# stm8core.net
KiCad netlist of a schematic drawn in Altium Designer
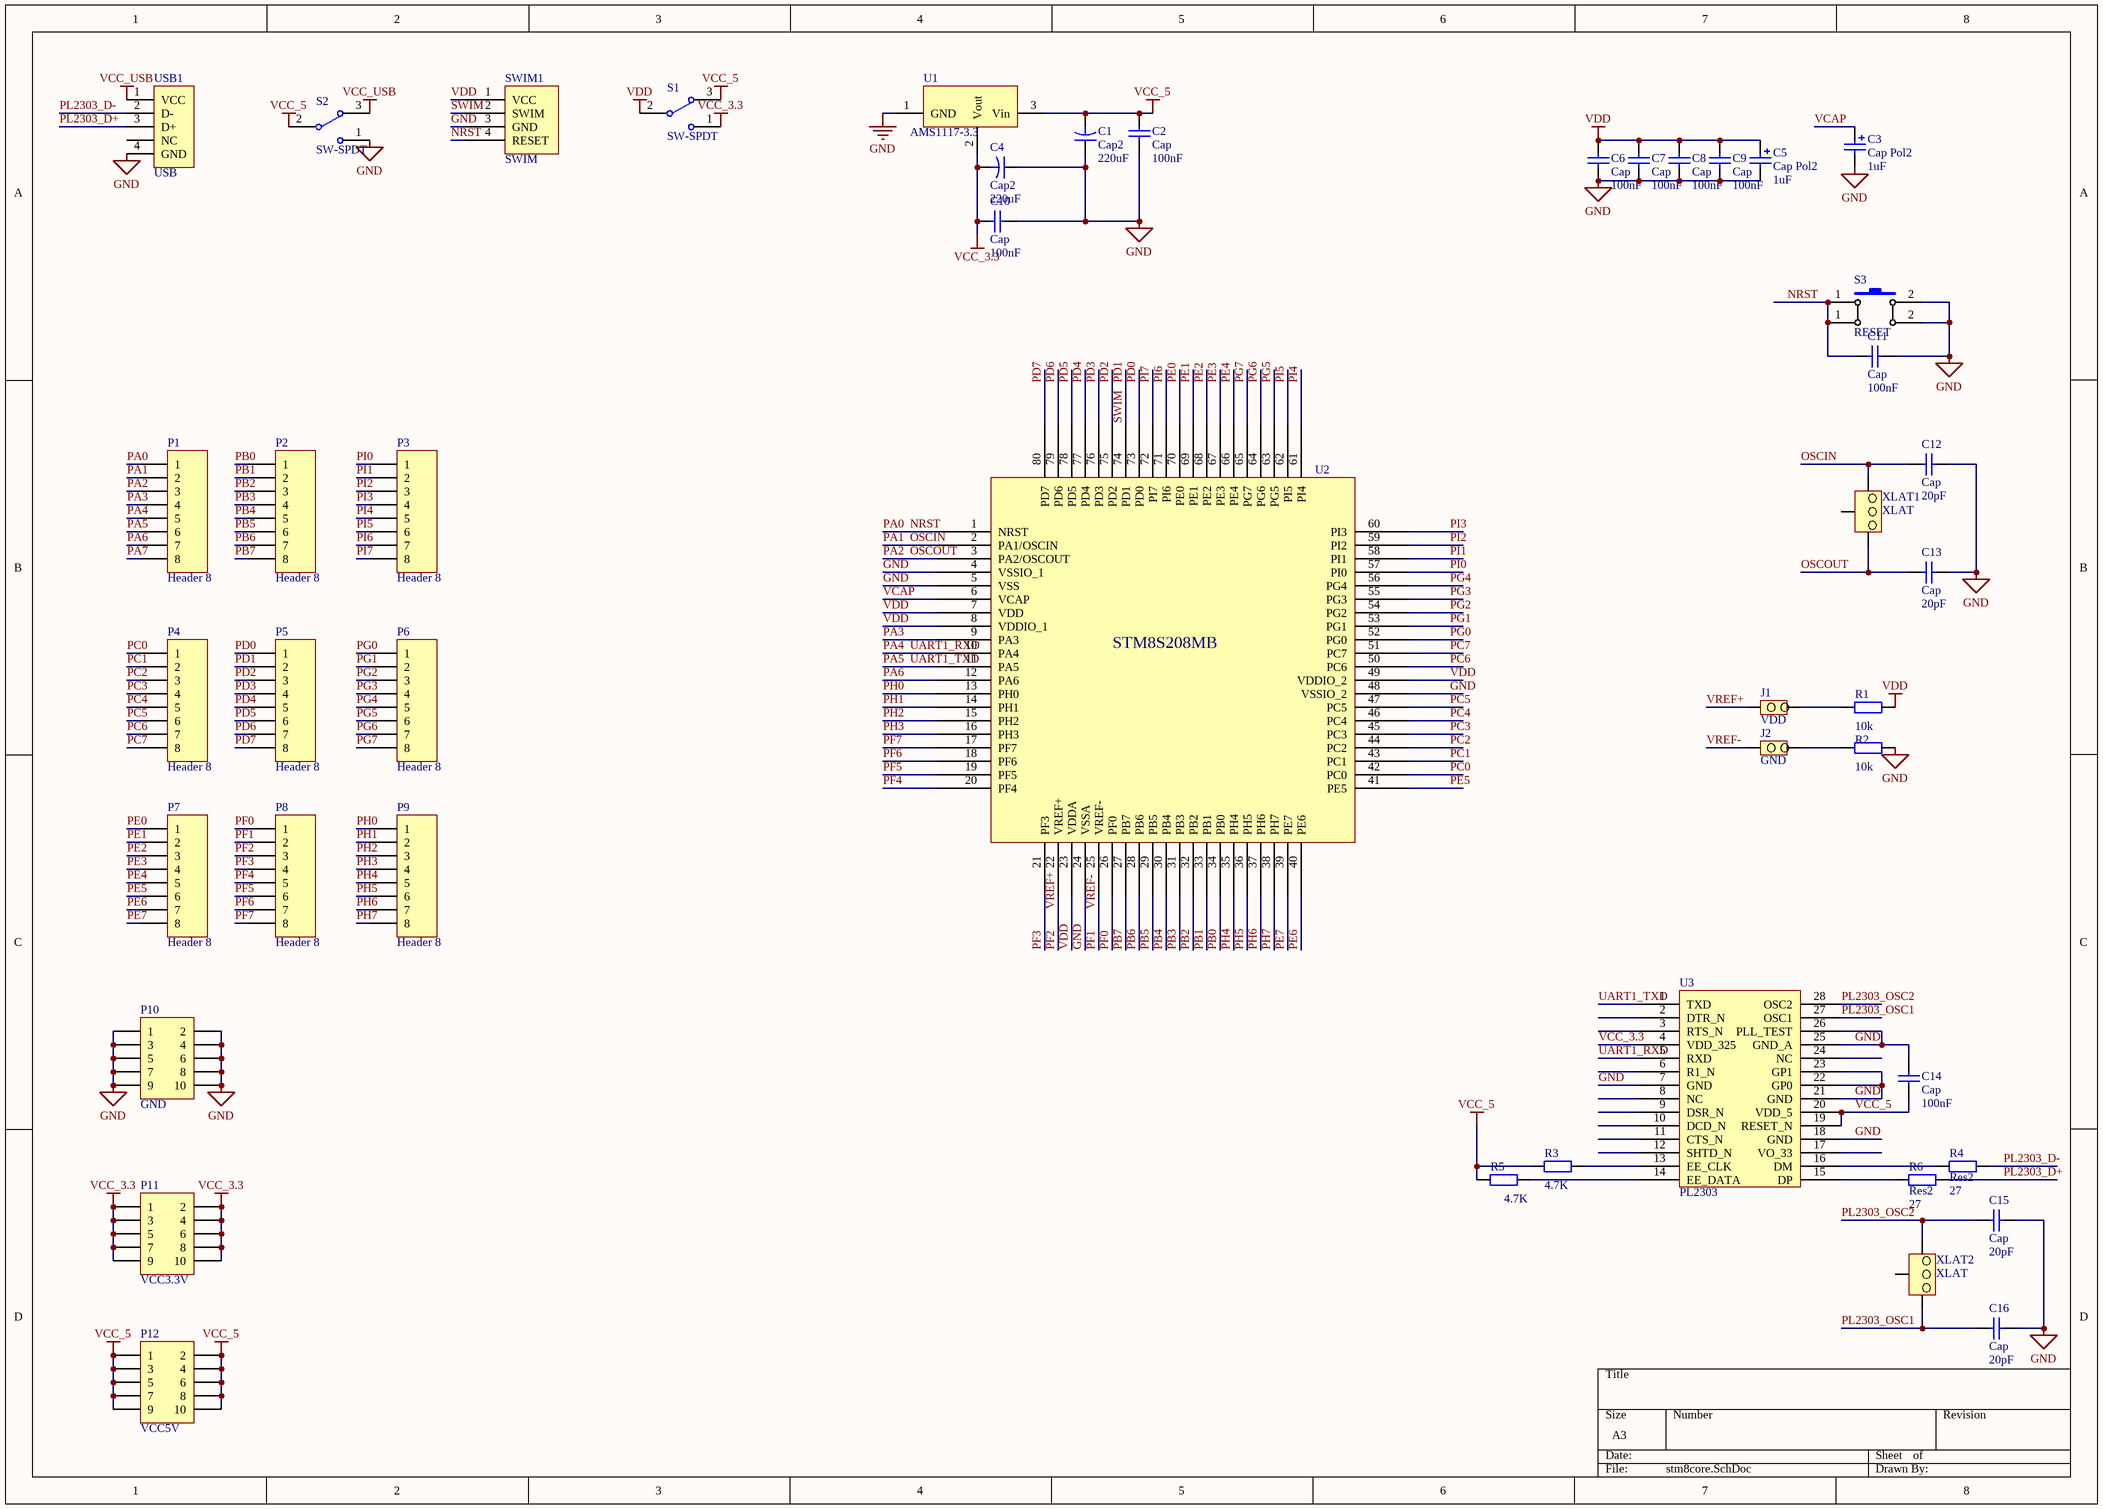
[diagram p0: stm8core.SchDoc]

(export (version "E")
  (design (tool "Eeschema 10.0.6"))
  (components
    (comp (ref "C1")
      (value "Cap2")
      (footprint "RB-.1/.3")
      (description "Capacitor")
      (fields (field (name "ALTIUM_VALUE") "220uF") (field (name "PUBLISHER") "Altium Limited"))
      (libsource (lib "Miscellaneous Devices") (part "Cap2"))
    )
    (comp (ref "C2")
      (value "Cap")
      (footprint "0603")
      (description "Capacitor")
      (fields (field (name "ALTIUM_VALUE") "100nF") (field (name "PUBLISHER") "Altium Limited"))
      (libsource (lib "Miscellaneous Devices") (part "Cap"))
    )
    (comp (ref "C3")
      (value "Cap Pol2")
      (footprint "3216")
      (description "Polarized Capacitor (Axial)")
      (fields (field (name "ALTIUM_VALUE") "1uF") (field (name "PUBLISHER") "Altium Limited"))
      (libsource (lib "Miscellaneous Devices") (part "Cap Pol2"))
    )
    (comp (ref "C4")
      (value "Cap2")
      (footprint "RB-.1/.3")
      (description "Capacitor")
      (fields (field (name "ALTIUM_VALUE") "220uF") (field (name "PUBLISHER") "Altium Limited"))
      (libsource (lib "Miscellaneous Devices") (part "Cap2"))
    )
    (comp (ref "C5")
      (value "Cap Pol2")
      (footprint "3216")
      (description "Polarized Capacitor (Axial)")
      (fields (field (name "ALTIUM_VALUE") "1uF") (field (name "PUBLISHER") "Altium Limited"))
      (libsource (lib "Miscellaneous Devices") (part "Cap Pol2"))
    )
    (comp (ref "C6")
      (value "Cap")
      (footprint "0603")
      (description "Capacitor")
      (fields (field (name "ALTIUM_VALUE") "100nF") (field (name "PUBLISHER") "Altium Limited"))
      (libsource (lib "Miscellaneous Devices") (part "Cap"))
    )
    (comp (ref "C7")
      (value "Cap")
      (footprint "0603")
      (description "Capacitor")
      (fields (field (name "ALTIUM_VALUE") "100nF") (field (name "PUBLISHER") "Altium Limited"))
      (libsource (lib "Miscellaneous Devices") (part "Cap"))
    )
    (comp (ref "C8")
      (value "Cap")
      (footprint "0603")
      (description "Capacitor")
      (fields (field (name "ALTIUM_VALUE") "100nF") (field (name "PUBLISHER") "Altium Limited"))
      (libsource (lib "Miscellaneous Devices") (part "Cap"))
    )
    (comp (ref "C9")
      (value "Cap")
      (footprint "0603")
      (description "Capacitor")
      (fields (field (name "ALTIUM_VALUE") "100nF") (field (name "PUBLISHER") "Altium Limited"))
      (libsource (lib "Miscellaneous Devices") (part "Cap"))
    )
    (comp (ref "C10")
      (value "Cap")
      (footprint "0603")
      (description "Capacitor")
      (fields (field (name "ALTIUM_VALUE") "100nF") (field (name "PUBLISHER") "Altium Limited"))
      (libsource (lib "Miscellaneous Devices") (part "Cap"))
    )
    (comp (ref "C11")
      (value "Cap")
      (footprint "0603")
      (description "Capacitor")
      (fields (field (name "ALTIUM_VALUE") "100nF") (field (name "PUBLISHER") "Altium Limited"))
      (libsource (lib "Miscellaneous Devices") (part "Cap"))
    )
    (comp (ref "C12")
      (value "Cap")
      (footprint "0603")
      (description "Capacitor")
      (fields (field (name "ALTIUM_VALUE") "20pF") (field (name "PUBLISHER") "Altium Limited"))
      (libsource (lib "Miscellaneous Devices") (part "Cap"))
    )
    (comp (ref "C13")
      (value "Cap")
      (footprint "0603")
      (description "Capacitor")
      (fields (field (name "ALTIUM_VALUE") "20pF") (field (name "PUBLISHER") "Altium Limited"))
      (libsource (lib "Miscellaneous Devices") (part "Cap"))
    )
    (comp (ref "C14")
      (value "Cap")
      (footprint "0603")
      (description "Capacitor")
      (fields (field (name "ALTIUM_VALUE") "100nF") (field (name "PUBLISHER") "Altium Limited"))
      (libsource (lib "Miscellaneous Devices") (part "Cap"))
    )
    (comp (ref "C15")
      (value "Cap")
      (footprint "0603")
      (description "Capacitor")
      (fields (field (name "ALTIUM_VALUE") "20pF") (field (name "PUBLISHER") "Altium Limited"))
      (libsource (lib "Miscellaneous Devices") (part "Cap"))
    )
    (comp (ref "C16")
      (value "Cap")
      (footprint "0603")
      (description "Capacitor")
      (fields (field (name "ALTIUM_VALUE") "20pF") (field (name "PUBLISHER") "Altium Limited"))
      (libsource (lib "Miscellaneous Devices") (part "Cap"))
    )
    (comp (ref "J1") (value "VDD") (footprint "jumper") (libsource (lib "slave") (part "JNMPER")))
    (comp (ref "J2") (value "GND") (footprint "jumper") (libsource (lib "slave") (part "JNMPER")))
    (comp (ref "P1")
      (value "Header 8")
      (footprint "SIP8")
      (description "Header, 8-Pin")
      (fields (field (name "PUBLISHER") "Altium Limited"))
      (libsource (lib "Miscellaneous Connectors") (part "Header 8"))
    )
    (comp (ref "P2")
      (value "Header 8")
      (footprint "SIP8")
      (description "Header, 8-Pin")
      (fields (field (name "PUBLISHER") "Altium Limited"))
      (libsource (lib "Miscellaneous Connectors") (part "Header 8"))
    )
    (comp (ref "P3")
      (value "Header 8")
      (footprint "SIP8")
      (description "Header, 8-Pin")
      (fields (field (name "PUBLISHER") "Altium Limited"))
      (libsource (lib "Miscellaneous Connectors") (part "Header 8"))
    )
    (comp (ref "P4")
      (value "Header 8")
      (footprint "SIP8")
      (description "Header, 8-Pin")
      (fields (field (name "PUBLISHER") "Altium Limited"))
      (libsource (lib "Miscellaneous Connectors") (part "Header 8"))
    )
    (comp (ref "P5")
      (value "Header 8")
      (footprint "SIP8")
      (description "Header, 8-Pin")
      (fields (field (name "PUBLISHER") "Altium Limited"))
      (libsource (lib "Miscellaneous Connectors") (part "Header 8"))
    )
    (comp (ref "P6")
      (value "Header 8")
      (footprint "SIP8")
      (description "Header, 8-Pin")
      (fields (field (name "PUBLISHER") "Altium Limited"))
      (libsource (lib "Miscellaneous Connectors") (part "Header 8"))
    )
    (comp (ref "P7")
      (value "Header 8")
      (footprint "SIP8")
      (description "Header, 8-Pin")
      (fields (field (name "PUBLISHER") "Altium Limited"))
      (libsource (lib "Miscellaneous Connectors") (part "Header 8"))
    )
    (comp (ref "P8")
      (value "Header 8")
      (footprint "SIP8")
      (description "Header, 8-Pin")
      (fields (field (name "PUBLISHER") "Altium Limited"))
      (libsource (lib "Miscellaneous Connectors") (part "Header 8"))
    )
    (comp (ref "P9")
      (value "Header 8")
      (footprint "SIP8")
      (description "Header, 8-Pin")
      (fields (field (name "PUBLISHER") "Altium Limited"))
      (libsource (lib "Miscellaneous Connectors") (part "Header 8"))
    )
    (comp (ref "P10")
      (value "GND")
      (footprint "HDR2X5")
      (description "Header, 5-Pin, Dual row")
      (fields (field (name "PUBLISHER") "Altium Limited"))
      (libsource (lib "Miscellaneous Connectors") (part "Header 5X2"))
    )
    (comp (ref "P11")
      (value "VCC3.3V")
      (footprint "HDR2X5")
      (description "Header, 5-Pin, Dual row")
      (fields (field (name "PUBLISHER") "Altium Limited"))
      (libsource (lib "Miscellaneous Connectors") (part "Header 5X2"))
    )
    (comp (ref "P12")
      (value "VCC5V")
      (footprint "HDR2X5")
      (description "Header, 5-Pin, Dual row")
      (fields (field (name "PUBLISHER") "Altium Limited"))
      (libsource (lib "Miscellaneous Connectors") (part "Header 5X2"))
    )
    (comp (ref "R1")
      (value "10k")
      (footprint "0603")
      (description "Resistor")
      (fields (field (name "Comment") "Res2") (field (name "PUBLISHER") "Altium Limited"))
      (libsource (lib "Miscellaneous Devices") (part "Res2"))
    )
    (comp (ref "R2")
      (value "10k")
      (footprint "0603")
      (description "Resistor")
      (fields (field (name "Comment") "Res2") (field (name "PUBLISHER") "Altium Limited"))
      (libsource (lib "Miscellaneous Devices") (part "Res2"))
    )
    (comp (ref "R3")
      (value "4.7K")
      (footprint "0603")
      (description "Resistor")
      (fields (field (name "Comment") "Res2") (field (name "PUBLISHER") "Altium Limited"))
      (libsource (lib "Miscellaneous Devices") (part "Res2"))
    )
    (comp (ref "R4")
      (value "Res2")
      (footprint "0603")
      (description "Resistor")
      (fields (field (name "ALTIUM_VALUE") "27") (field (name "PUBLISHER") "Altium Limited"))
      (libsource (lib "Miscellaneous Devices") (part "Res2"))
    )
    (comp (ref "R5")
      (value "4.7K")
      (footprint "0603")
      (description "Resistor")
      (fields (field (name "Comment") "Res2") (field (name "PUBLISHER") "Altium Limited"))
      (libsource (lib "Miscellaneous Devices") (part "Res2"))
    )
    (comp (ref "R6")
      (value "Res2")
      (footprint "0603")
      (description "Resistor")
      (fields (field (name "ALTIUM_VALUE") "27") (field (name "PUBLISHER") "Altium Limited"))
      (libsource (lib "Miscellaneous Devices") (part "Res2"))
    )
    (comp (ref "S1")
      (value "SW-SPDT")
      (footprint "sw3")
      (description "SPDT Subminiature Toggle Switch, Right Angle Mounting, Vertical Actuation")
      (fields (field (name "PUBLISHER") "Altium Limited"))
      (libsource (lib "Miscellaneous Devices") (part "SW-SPDT"))
    )
    (comp (ref "S2")
      (value "SW-SPDT")
      (footprint "sw3")
      (description "SPDT Subminiature Toggle Switch, Right Angle Mounting, Vertical Actuation")
      (fields (field (name "PUBLISHER") "Altium Limited"))
      (libsource (lib "Miscellaneous Devices") (part "SW-SPDT"))
    )
    (comp (ref "S3")
      (value "RESET")
      (footprint "SW-PB")
      (description "Switch")
      (fields (field (name "PUBLISHER") "Altium Limited"))
      (libsource (lib "schLIB") (part "SW-PB"))
    )
    (comp (ref "SWIM1") (value "SWIM") (footprint "SIP4") (libsource (lib "slave") (part "SWIM")))
    (comp (ref "U1") (value "AMS1117-3.3") (footprint "SOT-223") (libsource (lib "stm") (part "AMS1117-3.3")))
    (comp (ref "U2") (value "STM8S208MB") (footprint "LQFP80") (libsource (lib "电路设计_1") (part "STM8S208MB")))
    (comp (ref "U3") (value "PL2303") (footprint "SSOP28") (libsource (lib "slave") (part "PL2303")))
    (comp (ref "USB1") (value "USB") (footprint "mini_USB") (libsource (lib "schLIB") (part "USB")))
    (comp (ref "XLAT1") (value "XLAT") (footprint "XTAL") (libsource (lib "schLIB") (part "MYXLAT")))
    (comp (ref "XLAT2") (value "XLAT") (footprint "XTAL") (libsource (lib "schLIB") (part "MYXLAT")))
  )
  (nets
    (net (code "1") (name "/NRST") (class "Default")
      (node (ref "C11") (pin "1") (pinfunction "1_1") (pintype "passive"))
      (node (ref "P1") (pin "1") (pinfunction "1_1") (pintype "passive"))
      (node (ref "S3") (pin "1") (pinfunction "1_1") (pintype "passive"))
      (node (ref "SWIM1") (pin "4") (pinfunction "RESET_4") (pintype "passive"))
      (node (ref "U2") (pin "1") (pinfunction "NRST_1") (pintype "passive"))
    )
    (net (code "2") (name "/OSCIN") (class "Default")
      (node (ref "C12") (pin "1") (pinfunction "1_1") (pintype "passive"))
      (node (ref "P1") (pin "2") (pinfunction "2_2") (pintype "passive"))
      (node (ref "U2") (pin "2") (pinfunction "PA1/OSCIN_2") (pintype "passive"))
      (node (ref "XLAT1") (pin "1") (pinfunction "1_1") (pintype "passive"))
    )
    (net (code "3") (name "/OSCOUT") (class "Default")
      (node (ref "C13") (pin "1") (pinfunction "1_1") (pintype "passive"))
      (node (ref "P1") (pin "3") (pinfunction "3_3") (pintype "passive"))
      (node (ref "U2") (pin "3") (pinfunction "PA2/OSCOUT_3") (pintype "passive"))
      (node (ref "XLAT1") (pin "2") (pinfunction "2_2") (pintype "passive"))
    )
    (net (code "4") (name "/PA3") (class "Default")
      (node (ref "P1") (pin "4") (pinfunction "4_4") (pintype "passive"))
      (node (ref "U2") (pin "9") (pinfunction "PA3_9") (pintype "passive"))
    )
    (net (code "5") (name "/PA4") (class "Default")
      (node (ref "P1") (pin "5") (pinfunction "5_5") (pintype "passive"))
      (node (ref "U2") (pin "10") (pinfunction "PA4_10") (pintype "passive"))
      (node (ref "U3") (pin "5") (pinfunction "RXD_5") (pintype "passive"))
    )
    (net (code "6") (name "/PA5") (class "Default")
      (node (ref "P1") (pin "6") (pinfunction "6_6") (pintype "passive"))
      (node (ref "U2") (pin "11") (pinfunction "PA5_11") (pintype "passive"))
      (node (ref "U3") (pin "1") (pinfunction "TXD_1") (pintype "passive"))
    )
    (net (code "7") (name "/PA6") (class "Default")
      (node (ref "P1") (pin "7") (pinfunction "7_7") (pintype "passive"))
      (node (ref "U2") (pin "12") (pinfunction "PA6_12") (pintype "passive"))
    )
    (net (code "8") (name "/PA7") (class "Default")
      (node (ref "P1") (pin "8") (pinfunction "8_8") (pintype "passive"))
    )
    (net (code "9") (name "/PB0") (class "Default")
      (node (ref "P2") (pin "1") (pinfunction "1_1") (pintype "passive"))
      (node (ref "U2") (pin "34") (pinfunction "PB0_34") (pintype "passive"))
    )
    (net (code "10") (name "/PB1") (class "Default")
      (node (ref "P2") (pin "2") (pinfunction "2_2") (pintype "passive"))
      (node (ref "U2") (pin "33") (pinfunction "PB1_33") (pintype "passive"))
    )
    (net (code "11") (name "/PB2") (class "Default")
      (node (ref "P2") (pin "3") (pinfunction "3_3") (pintype "passive"))
      (node (ref "U2") (pin "32") (pinfunction "PB2_32") (pintype "passive"))
    )
    (net (code "12") (name "/PB3") (class "Default")
      (node (ref "P2") (pin "4") (pinfunction "4_4") (pintype "passive"))
      (node (ref "U2") (pin "31") (pinfunction "PB3_31") (pintype "passive"))
    )
    (net (code "13") (name "/PB4") (class "Default")
      (node (ref "P2") (pin "5") (pinfunction "5_5") (pintype "passive"))
      (node (ref "U2") (pin "30") (pinfunction "PB4_30") (pintype "passive"))
    )
    (net (code "14") (name "/PB5") (class "Default")
      (node (ref "P2") (pin "6") (pinfunction "6_6") (pintype "passive"))
      (node (ref "U2") (pin "29") (pinfunction "PB5_29") (pintype "passive"))
    )
    (net (code "15") (name "/PB6") (class "Default")
      (node (ref "P2") (pin "7") (pinfunction "7_7") (pintype "passive"))
      (node (ref "U2") (pin "28") (pinfunction "PB6_28") (pintype "passive"))
    )
    (net (code "16") (name "/PB7") (class "Default")
      (node (ref "P2") (pin "8") (pinfunction "8_8") (pintype "passive"))
      (node (ref "U2") (pin "27") (pinfunction "PB7_27") (pintype "passive"))
    )
    (net (code "17") (name "/PC0") (class "Default")
      (node (ref "P4") (pin "1") (pinfunction "1_1") (pintype "passive"))
      (node (ref "U2") (pin "42") (pinfunction "PC0_42") (pintype "passive"))
    )
    (net (code "18") (name "/PC1") (class "Default")
      (node (ref "P4") (pin "2") (pinfunction "2_2") (pintype "passive"))
      (node (ref "U2") (pin "43") (pinfunction "PC1_43") (pintype "passive"))
    )
    (net (code "19") (name "/PC2") (class "Default")
      (node (ref "P4") (pin "3") (pinfunction "3_3") (pintype "passive"))
      (node (ref "U2") (pin "44") (pinfunction "PC2_44") (pintype "passive"))
    )
    (net (code "20") (name "/PC3") (class "Default")
      (node (ref "P4") (pin "4") (pinfunction "4_4") (pintype "passive"))
      (node (ref "U2") (pin "45") (pinfunction "PC3_45") (pintype "passive"))
    )
    (net (code "21") (name "/PC4") (class "Default")
      (node (ref "P4") (pin "5") (pinfunction "5_5") (pintype "passive"))
      (node (ref "U2") (pin "46") (pinfunction "PC4_46") (pintype "passive"))
    )
    (net (code "22") (name "/PC5") (class "Default")
      (node (ref "P4") (pin "6") (pinfunction "6_6") (pintype "passive"))
      (node (ref "U2") (pin "47") (pinfunction "PC5_47") (pintype "passive"))
    )
    (net (code "23") (name "/PC6") (class "Default")
      (node (ref "P4") (pin "7") (pinfunction "7_7") (pintype "passive"))
      (node (ref "U2") (pin "50") (pinfunction "PC6_50") (pintype "passive"))
    )
    (net (code "24") (name "/PC7") (class "Default")
      (node (ref "P4") (pin "8") (pinfunction "8_8") (pintype "passive"))
      (node (ref "U2") (pin "51") (pinfunction "PC7_51") (pintype "passive"))
    )
    (net (code "25") (name "/PD0") (class "Default")
      (node (ref "P5") (pin "1") (pinfunction "1_1") (pintype "passive"))
      (node (ref "U2") (pin "73") (pinfunction "PD0_73") (pintype "passive"))
    )
    (net (code "26") (name "/PD1") (class "Default")
      (node (ref "P5") (pin "2") (pinfunction "2_2") (pintype "passive"))
      (node (ref "SWIM1") (pin "2") (pinfunction "SWIM_2") (pintype "passive"))
      (node (ref "U2") (pin "74") (pinfunction "PD1_74") (pintype "passive"))
    )
    (net (code "27") (name "/PD2") (class "Default")
      (node (ref "P5") (pin "3") (pinfunction "3_3") (pintype "passive"))
      (node (ref "U2") (pin "75") (pinfunction "PD2_75") (pintype "passive"))
    )
    (net (code "28") (name "/PD3") (class "Default")
      (node (ref "P5") (pin "4") (pinfunction "4_4") (pintype "passive"))
      (node (ref "U2") (pin "76") (pinfunction "PD3_76") (pintype "passive"))
    )
    (net (code "29") (name "/PD4") (class "Default")
      (node (ref "P5") (pin "5") (pinfunction "5_5") (pintype "passive"))
      (node (ref "U2") (pin "77") (pinfunction "PD4_77") (pintype "passive"))
    )
    (net (code "30") (name "/PD5") (class "Default")
      (node (ref "P5") (pin "6") (pinfunction "6_6") (pintype "passive"))
      (node (ref "U2") (pin "78") (pinfunction "PD5_78") (pintype "passive"))
    )
    (net (code "31") (name "/PD6") (class "Default")
      (node (ref "P5") (pin "7") (pinfunction "7_7") (pintype "passive"))
      (node (ref "U2") (pin "79") (pinfunction "PD6_79") (pintype "passive"))
    )
    (net (code "32") (name "/PD7") (class "Default")
      (node (ref "P5") (pin "8") (pinfunction "8_8") (pintype "passive"))
      (node (ref "U2") (pin "80") (pinfunction "PD7_80") (pintype "passive"))
    )
    (net (code "33") (name "/PE0") (class "Default")
      (node (ref "P7") (pin "1") (pinfunction "1_1") (pintype "passive"))
      (node (ref "U2") (pin "70") (pinfunction "PE0_70") (pintype "passive"))
    )
    (net (code "34") (name "/PE1") (class "Default")
      (node (ref "P7") (pin "2") (pinfunction "2_2") (pintype "passive"))
      (node (ref "U2") (pin "69") (pinfunction "PE1_69") (pintype "passive"))
    )
    (net (code "35") (name "/PE2") (class "Default")
      (node (ref "P7") (pin "3") (pinfunction "3_3") (pintype "passive"))
      (node (ref "U2") (pin "68") (pinfunction "PE2_68") (pintype "passive"))
    )
    (net (code "36") (name "/PE3") (class "Default")
      (node (ref "P7") (pin "4") (pinfunction "4_4") (pintype "passive"))
      (node (ref "U2") (pin "67") (pinfunction "PE3_67") (pintype "passive"))
    )
    (net (code "37") (name "/PE4") (class "Default")
      (node (ref "P7") (pin "5") (pinfunction "5_5") (pintype "passive"))
      (node (ref "U2") (pin "66") (pinfunction "PE4_66") (pintype "passive"))
    )
    (net (code "38") (name "/PE5") (class "Default")
      (node (ref "P7") (pin "6") (pinfunction "6_6") (pintype "passive"))
      (node (ref "U2") (pin "41") (pinfunction "PE5_41") (pintype "passive"))
    )
    (net (code "39") (name "/PE6") (class "Default")
      (node (ref "P7") (pin "7") (pinfunction "7_7") (pintype "passive"))
      (node (ref "U2") (pin "40") (pinfunction "PE6_40") (pintype "passive"))
    )
    (net (code "40") (name "/PE7") (class "Default")
      (node (ref "P7") (pin "8") (pinfunction "8_8") (pintype "passive"))
      (node (ref "U2") (pin "39") (pinfunction "PE7_39") (pintype "passive"))
    )
    (net (code "41") (name "/PF0") (class "Default")
      (node (ref "P8") (pin "1") (pinfunction "1_1") (pintype "passive"))
      (node (ref "U2") (pin "26") (pinfunction "PF0_26") (pintype "passive"))
    )
    (net (code "42") (name "/PF1") (class "Default")
      (node (ref "J2") (pin "1") (pinfunction "1_1") (pintype "passive"))
      (node (ref "P8") (pin "2") (pinfunction "2_2") (pintype "passive"))
      (node (ref "U2") (pin "25") (pinfunction "VREF-_25") (pintype "passive"))
    )
    (net (code "43") (name "/PF2") (class "Default")
      (node (ref "J1") (pin "1") (pinfunction "1_1") (pintype "passive"))
      (node (ref "P8") (pin "3") (pinfunction "3_3") (pintype "passive"))
      (node (ref "U2") (pin "22") (pinfunction "VREF+_22") (pintype "passive"))
    )
    (net (code "44") (name "/PF3") (class "Default")
      (node (ref "P8") (pin "4") (pinfunction "4_4") (pintype "passive"))
      (node (ref "U2") (pin "21") (pinfunction "PF3_21") (pintype "passive"))
    )
    (net (code "45") (name "/PF4") (class "Default")
      (node (ref "P8") (pin "5") (pinfunction "5_5") (pintype "passive"))
      (node (ref "U2") (pin "20") (pinfunction "PF4_20") (pintype "passive"))
    )
    (net (code "46") (name "/PF5") (class "Default")
      (node (ref "P8") (pin "6") (pinfunction "6_6") (pintype "passive"))
      (node (ref "U2") (pin "19") (pinfunction "PF5_19") (pintype "passive"))
    )
    (net (code "47") (name "/PF6") (class "Default")
      (node (ref "P8") (pin "7") (pinfunction "7_7") (pintype "passive"))
      (node (ref "U2") (pin "18") (pinfunction "PF6_18") (pintype "passive"))
    )
    (net (code "48") (name "/PF7") (class "Default")
      (node (ref "P8") (pin "8") (pinfunction "8_8") (pintype "passive"))
      (node (ref "U2") (pin "17") (pinfunction "PF7_17") (pintype "passive"))
    )
    (net (code "49") (name "/PG0") (class "Default")
      (node (ref "P6") (pin "1") (pinfunction "1_1") (pintype "passive"))
      (node (ref "U2") (pin "52") (pinfunction "PG0_52") (pintype "passive"))
    )
    (net (code "50") (name "/PG1") (class "Default")
      (node (ref "P6") (pin "2") (pinfunction "2_2") (pintype "passive"))
      (node (ref "U2") (pin "53") (pinfunction "PG1_53") (pintype "passive"))
    )
    (net (code "51") (name "/PG2") (class "Default")
      (node (ref "P6") (pin "3") (pinfunction "3_3") (pintype "passive"))
      (node (ref "U2") (pin "54") (pinfunction "PG2_54") (pintype "passive"))
    )
    (net (code "52") (name "/PG3") (class "Default")
      (node (ref "P6") (pin "4") (pinfunction "4_4") (pintype "passive"))
      (node (ref "U2") (pin "55") (pinfunction "PG3_55") (pintype "passive"))
    )
    (net (code "53") (name "/PG4") (class "Default")
      (node (ref "P6") (pin "5") (pinfunction "5_5") (pintype "passive"))
      (node (ref "U2") (pin "56") (pinfunction "PG4_56") (pintype "passive"))
    )
    (net (code "54") (name "/PG5") (class "Default")
      (node (ref "P6") (pin "6") (pinfunction "6_6") (pintype "passive"))
      (node (ref "U2") (pin "63") (pinfunction "PG5_63") (pintype "passive"))
    )
    (net (code "55") (name "/PG6") (class "Default")
      (node (ref "P6") (pin "7") (pinfunction "7_7") (pintype "passive"))
      (node (ref "U2") (pin "64") (pinfunction "PG6_64") (pintype "passive"))
    )
    (net (code "56") (name "/PG7") (class "Default")
      (node (ref "P6") (pin "8") (pinfunction "8_8") (pintype "passive"))
      (node (ref "U2") (pin "65") (pinfunction "PG7_65") (pintype "passive"))
    )
    (net (code "57") (name "/PH0") (class "Default")
      (node (ref "P9") (pin "1") (pinfunction "1_1") (pintype "passive"))
      (node (ref "U2") (pin "13") (pinfunction "PH0_13") (pintype "passive"))
    )
    (net (code "58") (name "/PH1") (class "Default")
      (node (ref "P9") (pin "2") (pinfunction "2_2") (pintype "passive"))
      (node (ref "U2") (pin "14") (pinfunction "PH1_14") (pintype "passive"))
    )
    (net (code "59") (name "/PH2") (class "Default")
      (node (ref "P9") (pin "3") (pinfunction "3_3") (pintype "passive"))
      (node (ref "U2") (pin "15") (pinfunction "PH2_15") (pintype "passive"))
    )
    (net (code "60") (name "/PH3") (class "Default")
      (node (ref "P9") (pin "4") (pinfunction "4_4") (pintype "passive"))
      (node (ref "U2") (pin "16") (pinfunction "PH3_16") (pintype "passive"))
    )
    (net (code "61") (name "/PH4") (class "Default")
      (node (ref "P9") (pin "5") (pinfunction "5_5") (pintype "passive"))
      (node (ref "U2") (pin "35") (pinfunction "PH4_35") (pintype "passive"))
    )
    (net (code "62") (name "/PH5") (class "Default")
      (node (ref "P9") (pin "6") (pinfunction "6_6") (pintype "passive"))
      (node (ref "U2") (pin "36") (pinfunction "PH5_36") (pintype "passive"))
    )
    (net (code "63") (name "/PH6") (class "Default")
      (node (ref "P9") (pin "7") (pinfunction "7_7") (pintype "passive"))
      (node (ref "U2") (pin "37") (pinfunction "PH6_37") (pintype "passive"))
    )
    (net (code "64") (name "/PH7") (class "Default")
      (node (ref "P9") (pin "8") (pinfunction "8_8") (pintype "passive"))
      (node (ref "U2") (pin "38") (pinfunction "PH7_38") (pintype "passive"))
    )
    (net (code "65") (name "/PI0") (class "Default")
      (node (ref "P3") (pin "1") (pinfunction "1_1") (pintype "passive"))
      (node (ref "U2") (pin "57") (pinfunction "PI0_57") (pintype "passive"))
    )
    (net (code "66") (name "/PI1") (class "Default")
      (node (ref "P3") (pin "2") (pinfunction "2_2") (pintype "passive"))
      (node (ref "U2") (pin "58") (pinfunction "PI1_58") (pintype "passive"))
    )
    (net (code "67") (name "/PI2") (class "Default")
      (node (ref "P3") (pin "3") (pinfunction "3_3") (pintype "passive"))
      (node (ref "U2") (pin "59") (pinfunction "PI2_59") (pintype "passive"))
    )
    (net (code "68") (name "/PI3") (class "Default")
      (node (ref "P3") (pin "4") (pinfunction "4_4") (pintype "passive"))
      (node (ref "U2") (pin "60") (pinfunction "PI3_60") (pintype "passive"))
    )
    (net (code "69") (name "/PI4") (class "Default")
      (node (ref "P3") (pin "5") (pinfunction "5_5") (pintype "passive"))
      (node (ref "U2") (pin "61") (pinfunction "PI4_61") (pintype "passive"))
    )
    (net (code "70") (name "/PI5") (class "Default")
      (node (ref "P3") (pin "6") (pinfunction "6_6") (pintype "passive"))
      (node (ref "U2") (pin "62") (pinfunction "PI5_62") (pintype "passive"))
    )
    (net (code "71") (name "/PI6") (class "Default")
      (node (ref "P3") (pin "7") (pinfunction "7_7") (pintype "passive"))
      (node (ref "U2") (pin "71") (pinfunction "PI6_71") (pintype "passive"))
    )
    (net (code "72") (name "/PI7") (class "Default")
      (node (ref "P3") (pin "8") (pinfunction "8_8") (pintype "passive"))
      (node (ref "U2") (pin "72") (pinfunction "PI7_72") (pintype "passive"))
    )
    (net (code "73") (name "/PL2303_D+") (class "Default")
      (node (ref "R6") (pin "2") (pinfunction "2_2") (pintype "passive"))
      (node (ref "USB1") (pin "3") (pinfunction "D+_3") (pintype "passive"))
    )
    (net (code "74") (name "/PL2303_D-") (class "Default")
      (node (ref "R4") (pin "2") (pinfunction "2_2") (pintype "passive"))
      (node (ref "USB1") (pin "2") (pinfunction "D-_2") (pintype "passive"))
    )
    (net (code "75") (name "/PL2303_OSC1") (class "Default")
      (node (ref "C16") (pin "1") (pinfunction "1_1") (pintype "passive"))
      (node (ref "U3") (pin "27") (pinfunction "OSC1_27") (pintype "passive"))
      (node (ref "XLAT2") (pin "2") (pinfunction "2_2") (pintype "passive"))
    )
    (net (code "76") (name "/PL2303_OSC2") (class "Default")
      (node (ref "C15") (pin "1") (pinfunction "1_1") (pintype "passive"))
      (node (ref "U3") (pin "28") (pinfunction "OSC2_28") (pintype "passive"))
      (node (ref "XLAT2") (pin "1") (pinfunction "1_1") (pintype "passive"))
    )
    (net (code "77") (name "/VCAP") (class "Default")
      (node (ref "C3") (pin "1") (pinfunction "1_1") (pintype "passive"))
      (node (ref "U2") (pin "6") (pinfunction "VCAP_6") (pintype "passive"))
    )
    (net (code "78") (name "GND") (class "Default")
      (node (ref "C1") (pin "1") (pinfunction "1_1") (pintype "passive"))
      (node (ref "C10") (pin "1") (pinfunction "1_1") (pintype "passive"))
      (node (ref "C11") (pin "2") (pinfunction "2_2") (pintype "passive"))
      (node (ref "C12") (pin "2") (pinfunction "2_2") (pintype "passive"))
      (node (ref "C13") (pin "2") (pinfunction "2_2") (pintype "passive"))
      (node (ref "C14") (pin "2") (pinfunction "2_2") (pintype "passive"))
      (node (ref "C15") (pin "2") (pinfunction "2_2") (pintype "passive"))
      (node (ref "C16") (pin "2") (pinfunction "2_2") (pintype "passive"))
      (node (ref "C2") (pin "1") (pinfunction "1_1") (pintype "passive"))
      (node (ref "C3") (pin "2") (pinfunction "2_2") (pintype "passive"))
      (node (ref "C4") (pin "1") (pinfunction "1_1") (pintype "passive"))
      (node (ref "C5") (pin "2") (pinfunction "2_2") (pintype "passive"))
      (node (ref "C6") (pin "1") (pinfunction "1_1") (pintype "passive"))
      (node (ref "C7") (pin "1") (pinfunction "1_1") (pintype "passive"))
      (node (ref "C8") (pin "1") (pinfunction "1_1") (pintype "passive"))
      (node (ref "C9") (pin "1") (pinfunction "1_1") (pintype "passive"))
      (node (ref "P10") (pin "1") (pinfunction "1_1") (pintype "passive"))
      (node (ref "P10") (pin "10") (pinfunction "10_10") (pintype "passive"))
      (node (ref "P10") (pin "2") (pinfunction "2_2") (pintype "passive"))
      (node (ref "P10") (pin "3") (pinfunction "3_3") (pintype "passive"))
      (node (ref "P10") (pin "4") (pinfunction "4_4") (pintype "passive"))
      (node (ref "P10") (pin "5") (pinfunction "5_5") (pintype "passive"))
      (node (ref "P10") (pin "6") (pinfunction "6_6") (pintype "passive"))
      (node (ref "P10") (pin "7") (pinfunction "7_7") (pintype "passive"))
      (node (ref "P10") (pin "8") (pinfunction "8_8") (pintype "passive"))
      (node (ref "P10") (pin "9") (pinfunction "9_9") (pintype "passive"))
      (node (ref "R2") (pin "2") (pinfunction "2_2") (pintype "passive"))
      (node (ref "S2") (pin "1") (pinfunction "1_1") (pintype "passive"))
      (node (ref "S3") (pin "2") (pinfunction "2_2") (pintype "passive"))
      (node (ref "SWIM1") (pin "3") (pinfunction "GND_3") (pintype "passive"))
      (node (ref "U1") (pin "1") (pinfunction "GND_1") (pintype "passive"))
      (node (ref "U2") (pin "24") (pinfunction "VSSA_24") (pintype "passive"))
      (node (ref "U2") (pin "4") (pinfunction "VSSIO_1_4") (pintype "passive"))
      (node (ref "U2") (pin "48") (pinfunction "VSSIO_2_48") (pintype "passive"))
      (node (ref "U2") (pin "5") (pinfunction "VSS_5") (pintype "passive"))
      (node (ref "U3") (pin "18") (pinfunction "GND_18") (pintype "passive"))
      (node (ref "U3") (pin "21") (pinfunction "GND_21") (pintype "passive"))
      (node (ref "U3") (pin "22") (pinfunction "GP0_22") (pintype "passive"))
      (node (ref "U3") (pin "23") (pinfunction "GP1_23") (pintype "passive"))
      (node (ref "U3") (pin "25") (pinfunction "GND_A_25") (pintype "passive"))
      (node (ref "U3") (pin "26") (pinfunction "PLL_TEST_26") (pintype "passive"))
      (node (ref "U3") (pin "7") (pinfunction "GND_7") (pintype "passive"))
      (node (ref "USB1") (pin "4") (pinfunction "GND_4") (pintype "passive"))
    )
    (net (code "79") (name "Net-(J1-Pad2)") (class "Default")
      (node (ref "J1") (pin "2") (pinfunction "2_2") (pintype "passive"))
      (node (ref "R1") (pin "1") (pinfunction "1_1") (pintype "passive"))
    )
    (net (code "80") (name "Net-(J2-Pad2)") (class "Default")
      (node (ref "J2") (pin "2") (pinfunction "2_2") (pintype "passive"))
      (node (ref "R2") (pin "1") (pinfunction "1_1") (pintype "passive"))
    )
    (net (code "81") (name "Net-(U3-DM)") (class "Default")
      (node (ref "R4") (pin "1") (pinfunction "1_1") (pintype "passive"))
      (node (ref "U3") (pin "16") (pinfunction "DM_16") (pintype "passive"))
    )
    (net (code "82") (name "Net-(U3-DP)") (class "Default")
      (node (ref "R6") (pin "1") (pinfunction "1_1") (pintype "passive"))
      (node (ref "U3") (pin "15") (pinfunction "DP_15") (pintype "passive"))
    )
    (net (code "83") (name "Net-(U3-EE_CLK)") (class "Default")
      (node (ref "R3") (pin "2") (pinfunction "2_2") (pintype "passive"))
      (node (ref "U3") (pin "13") (pinfunction "EE_CLK_13") (pintype "passive"))
    )
    (net (code "84") (name "Net-(U3-EE_DATA)") (class "Default")
      (node (ref "R5") (pin "2") (pinfunction "2_2") (pintype "passive"))
      (node (ref "U3") (pin "14") (pinfunction "EE_DATA_14") (pintype "passive"))
    )
    (net (code "85") (name "VCC_3.3") (class "Default")
      (node (ref "C10") (pin "2") (pinfunction "2_2") (pintype "passive"))
      (node (ref "C4") (pin "2") (pinfunction "2_2") (pintype "passive"))
      (node (ref "P11") (pin "1") (pinfunction "1_1") (pintype "passive"))
      (node (ref "P11") (pin "10") (pinfunction "10_10") (pintype "passive"))
      (node (ref "P11") (pin "2") (pinfunction "2_2") (pintype "passive"))
      (node (ref "P11") (pin "3") (pinfunction "3_3") (pintype "passive"))
      (node (ref "P11") (pin "4") (pinfunction "4_4") (pintype "passive"))
      (node (ref "P11") (pin "5") (pinfunction "5_5") (pintype "passive"))
      (node (ref "P11") (pin "6") (pinfunction "6_6") (pintype "passive"))
      (node (ref "P11") (pin "7") (pinfunction "7_7") (pintype "passive"))
      (node (ref "P11") (pin "8") (pinfunction "8_8") (pintype "passive"))
      (node (ref "P11") (pin "9") (pinfunction "9_9") (pintype "passive"))
      (node (ref "S1") (pin "1") (pinfunction "1_1") (pintype "passive"))
      (node (ref "U1") (pin "2") (pinfunction "Vout_2") (pintype "passive"))
      (node (ref "U3") (pin "4") (pinfunction "VDD_325_4") (pintype "passive"))
    )
    (net (code "86") (name "VCC_5") (class "Default")
      (node (ref "C1") (pin "2") (pinfunction "2_2") (pintype "passive"))
      (node (ref "C14") (pin "1") (pinfunction "1_1") (pintype "passive"))
      (node (ref "C2") (pin "2") (pinfunction "2_2") (pintype "passive"))
      (node (ref "P12") (pin "1") (pinfunction "1_1") (pintype "passive"))
      (node (ref "P12") (pin "10") (pinfunction "10_10") (pintype "passive"))
      (node (ref "P12") (pin "2") (pinfunction "2_2") (pintype "passive"))
      (node (ref "P12") (pin "3") (pinfunction "3_3") (pintype "passive"))
      (node (ref "P12") (pin "4") (pinfunction "4_4") (pintype "passive"))
      (node (ref "P12") (pin "5") (pinfunction "5_5") (pintype "passive"))
      (node (ref "P12") (pin "6") (pinfunction "6_6") (pintype "passive"))
      (node (ref "P12") (pin "7") (pinfunction "7_7") (pintype "passive"))
      (node (ref "P12") (pin "8") (pinfunction "8_8") (pintype "passive"))
      (node (ref "P12") (pin "9") (pinfunction "9_9") (pintype "passive"))
      (node (ref "R3") (pin "1") (pinfunction "1_1") (pintype "passive"))
      (node (ref "R5") (pin "1") (pinfunction "1_1") (pintype "passive"))
      (node (ref "S1") (pin "3") (pinfunction "3_3") (pintype "passive"))
      (node (ref "S2") (pin "2") (pinfunction "2_2") (pintype "passive"))
      (node (ref "U1") (pin "3") (pinfunction "Vin_3") (pintype "passive"))
      (node (ref "U3") (pin "19") (pinfunction "RESET_N_19") (pintype "passive"))
      (node (ref "U3") (pin "20") (pinfunction "VDD_5_20") (pintype "passive"))
    )
    (net (code "87") (name "VCC_USB") (class "Default")
      (node (ref "S2") (pin "3") (pinfunction "3_3") (pintype "passive"))
      (node (ref "USB1") (pin "1") (pinfunction "VCC_1") (pintype "passive"))
    )
    (net (code "88") (name "VDD") (class "Default")
      (node (ref "C5") (pin "1") (pinfunction "1_1") (pintype "passive"))
      (node (ref "C6") (pin "2") (pinfunction "2_2") (pintype "passive"))
      (node (ref "C7") (pin "2") (pinfunction "2_2") (pintype "passive"))
      (node (ref "C8") (pin "2") (pinfunction "2_2") (pintype "passive"))
      (node (ref "C9") (pin "2") (pinfunction "2_2") (pintype "passive"))
      (node (ref "R1") (pin "2") (pinfunction "2_2") (pintype "passive"))
      (node (ref "S1") (pin "2") (pinfunction "2_2") (pintype "passive"))
      (node (ref "SWIM1") (pin "1") (pinfunction "VCC_1") (pintype "passive"))
      (node (ref "U2") (pin "23") (pinfunction "VDDA_23") (pintype "passive"))
      (node (ref "U2") (pin "49") (pinfunction "VDDIO_2_49") (pintype "passive"))
      (node (ref "U2") (pin "7") (pinfunction "VDD_7") (pintype "passive"))
      (node (ref "U2") (pin "8") (pinfunction "VDDIO_1_8") (pintype "passive"))
    )
    (net (code "89") (name "unconnected-(U3-CTS_N-Pad11)") (class "Default")
      (node (ref "U3") (pin "11") (pinfunction "CTS_N_11") (pintype "passive"))
    )
    (net (code "90") (name "unconnected-(U3-DCD_N-Pad10)") (class "Default")
      (node (ref "U3") (pin "10") (pinfunction "DCD_N_10") (pintype "passive"))
    )
    (net (code "91") (name "unconnected-(U3-DSR_N-Pad9)") (class "Default")
      (node (ref "U3") (pin "9") (pinfunction "DSR_N_9") (pintype "passive"))
    )
    (net (code "92") (name "unconnected-(U3-DTR_N-Pad2)") (class "Default")
      (node (ref "U3") (pin "2") (pinfunction "DTR_N_2") (pintype "passive"))
    )
    (net (code "93") (name "unconnected-(U3-NC-Pad8)") (class "Default")
      (node (ref "U3") (pin "8") (pinfunction "NC_8") (pintype "passive"))
    )
    (net (code "94") (name "unconnected-(U3-NC-Pad24)") (class "Default")
      (node (ref "U3") (pin "24") (pinfunction "NC_24") (pintype "passive"))
    )
    (net (code "95") (name "unconnected-(U3-R1_N-Pad6)") (class "Default")
      (node (ref "U3") (pin "6") (pinfunction "R1_N_6") (pintype "passive"))
    )
    (net (code "96") (name "unconnected-(U3-RTS_N-Pad3)") (class "Default")
      (node (ref "U3") (pin "3") (pinfunction "RTS_N_3") (pintype "passive"))
    )
    (net (code "97") (name "unconnected-(U3-SHTD_N-Pad12)") (class "Default")
      (node (ref "U3") (pin "12") (pinfunction "SHTD_N_12") (pintype "passive"))
    )
    (net (code "98") (name "unconnected-(U3-VO_33-Pad17)") (class "Default")
      (node (ref "U3") (pin "17") (pinfunction "VO_33_17") (pintype "passive"))
    )
    (net (code "99") (name "unconnected-(USB1-NC-Pad)") (class "Default")
      (node (ref "USB1") (pin "") (pinfunction "NC_") (pintype "passive"))
    )
    (net (code "100") (name "unconnected-(XLAT1-Pad)") (class "Default")
      (node (ref "XLAT1") (pin "") (pintype "passive"))
    )
    (net (code "101") (name "unconnected-(XLAT2-Pad)") (class "Default")
      (node (ref "XLAT2") (pin "") (pintype "passive"))
    )
  )
)
